# xmas_v2.net
KiCad netlist of a schematic drawn in EAGLE
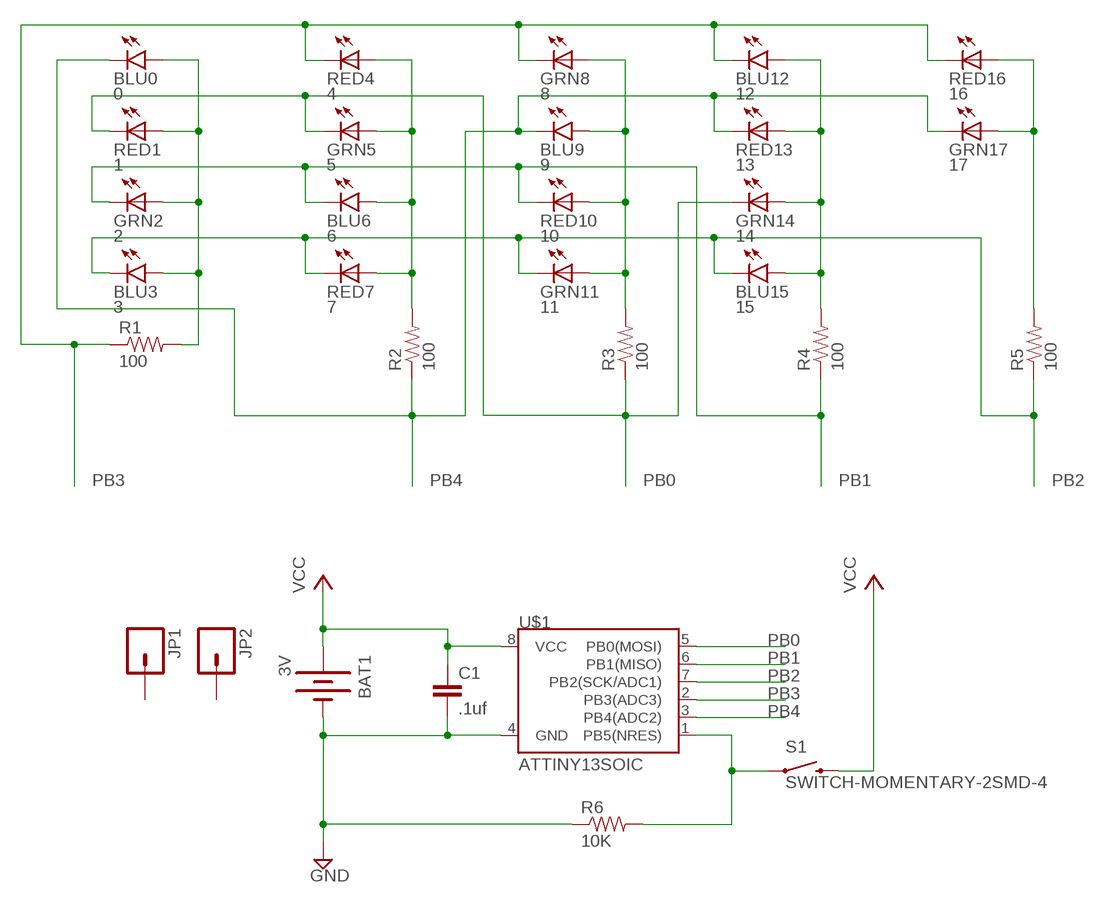
[diagram p0: schematic, sheet 1]

(export (version "E")
  (design (tool "Eeschema 10.0.6"))
  (components
    (comp (ref "BAT1")
      (value "3V")
      (footprint "eagle-import:BATTCOM_20MM_PTH")
      (libsource (lib "eagle-import") (part "BATTERY20PTH"))
    )
    (comp (ref "BLU0")
      (value "0")
      (footprint "eagle-import:LED5MM-KIT")
      (libsource (lib "eagle-import") (part "LED5MM-KIT"))
    )
    (comp (ref "BLU3")
      (value "3")
      (footprint "eagle-import:LED5MM-KIT")
      (libsource (lib "eagle-import") (part "LED5MM-KIT"))
    )
    (comp (ref "BLU6")
      (value "6")
      (footprint "eagle-import:LED5MM-KIT")
      (libsource (lib "eagle-import") (part "LED5MM-KIT"))
    )
    (comp (ref "BLU9")
      (value "9")
      (footprint "eagle-import:LED5MM-KIT")
      (libsource (lib "eagle-import") (part "LED5MM-KIT"))
    )
    (comp (ref "BLU12")
      (value "12")
      (footprint "eagle-import:LED5MM-KIT")
      (libsource (lib "eagle-import") (part "LED5MM-KIT"))
    )
    (comp (ref "BLU15")
      (value "15")
      (footprint "eagle-import:LED5MM-KIT")
      (libsource (lib "eagle-import") (part "LED5MM-KIT"))
    )
    (comp (ref "C1")
      (value ".1uf")
      (footprint "eagle-import:0805")
      (libsource (lib "eagle-import") (part "CAP0805"))
    )
    (comp (ref "GRN2")
      (value "2")
      (footprint "eagle-import:CHIPLED_0805")
      (libsource (lib "eagle-import") (part "LEDCHIPLED_0805"))
    )
    (comp (ref "GRN5")
      (value "5")
      (footprint "eagle-import:CHIPLED_0805")
      (libsource (lib "eagle-import") (part "LEDCHIPLED_0805"))
    )
    (comp (ref "GRN8")
      (value "8")
      (footprint "eagle-import:CHIPLED_0805")
      (libsource (lib "eagle-import") (part "LEDCHIPLED_0805"))
    )
    (comp (ref "GRN11")
      (value "11")
      (footprint "eagle-import:CHIPLED_0805")
      (libsource (lib "eagle-import") (part "LEDCHIPLED_0805"))
    )
    (comp (ref "GRN14")
      (value "14")
      (footprint "eagle-import:CHIPLED_0805")
      (libsource (lib "eagle-import") (part "LEDCHIPLED_0805"))
    )
    (comp (ref "GRN17")
      (value "17")
      (footprint "eagle-import:CHIPLED_0805")
      (libsource (lib "eagle-import") (part "LEDCHIPLED_0805"))
    )
    (comp (ref "JP1")
      (value "M01NOSILK-KIT")
      (footprint "eagle-import:1X01NS-KIT")
      (libsource (lib "eagle-import") (part "M01NOSILK-KIT"))
    )
    (comp (ref "JP2")
      (value "M01NOSILK-KIT")
      (footprint "eagle-import:1X01NS-KIT")
      (libsource (lib "eagle-import") (part "M01NOSILK-KIT"))
    )
    (comp (ref "R1")
      (value "100")
      (footprint "eagle-import:0805")
      (libsource (lib "eagle-import") (part "RESISTOR0805-RES"))
    )
    (comp (ref "R2")
      (value "100")
      (footprint "eagle-import:0805")
      (libsource (lib "eagle-import") (part "RESISTOR0805-RES"))
    )
    (comp (ref "R3")
      (value "100")
      (footprint "eagle-import:0805")
      (libsource (lib "eagle-import") (part "RESISTOR0805-RES"))
    )
    (comp (ref "R4")
      (value "100")
      (footprint "eagle-import:0805")
      (libsource (lib "eagle-import") (part "RESISTOR0805-RES"))
    )
    (comp (ref "R5")
      (value "100")
      (footprint "eagle-import:0805")
      (libsource (lib "eagle-import") (part "RESISTOR0805-RES"))
    )
    (comp (ref "R6")
      (value "10K")
      (footprint "eagle-import:0805")
      (libsource (lib "eagle-import") (part "RESISTOR0805-RES"))
    )
    (comp (ref "RED1")
      (value "1")
      (footprint "eagle-import:CHIPLED_0805")
      (libsource (lib "eagle-import") (part "LEDCHIPLED_0805"))
    )
    (comp (ref "RED4")
      (value "4")
      (footprint "eagle-import:CHIPLED_0805")
      (libsource (lib "eagle-import") (part "LEDCHIPLED_0805"))
    )
    (comp (ref "RED7")
      (value "7")
      (footprint "eagle-import:CHIPLED_0805")
      (libsource (lib "eagle-import") (part "LEDCHIPLED_0805"))
    )
    (comp (ref "RED10")
      (value "10")
      (footprint "eagle-import:CHIPLED_0805")
      (libsource (lib "eagle-import") (part "LEDCHIPLED_0805"))
    )
    (comp (ref "RED13")
      (value "13")
      (footprint "eagle-import:CHIPLED_0805")
      (libsource (lib "eagle-import") (part "LEDCHIPLED_0805"))
    )
    (comp (ref "RED16")
      (value "16")
      (footprint "eagle-import:CHIPLED_0805")
      (libsource (lib "eagle-import") (part "LEDCHIPLED_0805"))
    )
    (comp (ref "S1")
      (value "SWITCH-MOMENTARY-2SMD-4")
      (footprint "eagle-import:TACTILE_SWITCH_TALL")
      (libsource (lib "eagle-import") (part "SWITCH-MOMENTARY-2SMD-4"))
    )
    (comp (ref "U$1")
      (value "ATTINY13SOIC")
      (footprint "eagle-import:SO08")
      (libsource (lib "eagle-import") (part "ATTINY13SOIC"))
    )
  )
  (nets
    (net (code "1") (name "/PB0") (class "Default")
      (node (ref "GRN14") (pin "C") (pinfunction "C_C") (pintype "passive"))
      (node (ref "GRN5") (pin "C") (pinfunction "C_C") (pintype "passive"))
      (node (ref "R3") (pin "1") (pinfunction "1_1") (pintype "passive"))
      (node (ref "RED1") (pin "C") (pinfunction "C_C") (pintype "passive"))
      (node (ref "U$1") (pin "5") (pinfunction "PB0(MOSI)_5") (pintype "bidirectional"))
    )
    (net (code "2") (name "/PB1") (class "Default")
      (node (ref "BLU6") (pin "K") (pinfunction "C_K") (pintype "passive"))
      (node (ref "GRN2") (pin "C") (pinfunction "C_C") (pintype "passive"))
      (node (ref "R4") (pin "1") (pinfunction "1_1") (pintype "passive"))
      (node (ref "RED10") (pin "C") (pinfunction "C_C") (pintype "passive"))
      (node (ref "U$1") (pin "6") (pinfunction "PB1(MISO)_6") (pintype "bidirectional"))
    )
    (net (code "3") (name "/PB2") (class "Default")
      (node (ref "BLU15") (pin "K") (pinfunction "C_K") (pintype "passive"))
      (node (ref "BLU3") (pin "K") (pinfunction "C_K") (pintype "passive"))
      (node (ref "GRN11") (pin "C") (pinfunction "C_C") (pintype "passive"))
      (node (ref "R5") (pin "1") (pinfunction "1_1") (pintype "passive"))
      (node (ref "RED7") (pin "C") (pinfunction "C_C") (pintype "passive"))
      (node (ref "U$1") (pin "7") (pinfunction "PB2(SCK/ADC1)_7") (pintype "bidirectional"))
    )
    (net (code "4") (name "/PB3") (class "Default")
      (node (ref "BLU12") (pin "K") (pinfunction "C_K") (pintype "passive"))
      (node (ref "GRN8") (pin "C") (pinfunction "C_C") (pintype "passive"))
      (node (ref "R1") (pin "1") (pinfunction "1_1") (pintype "passive"))
      (node (ref "RED16") (pin "C") (pinfunction "C_C") (pintype "passive"))
      (node (ref "RED4") (pin "C") (pinfunction "C_C") (pintype "passive"))
      (node (ref "U$1") (pin "2") (pinfunction "PB3(ADC3)_2") (pintype "bidirectional"))
    )
    (net (code "5") (name "/PB4") (class "Default")
      (node (ref "BLU0") (pin "K") (pinfunction "C_K") (pintype "passive"))
      (node (ref "BLU9") (pin "K") (pinfunction "C_K") (pintype "passive"))
      (node (ref "GRN17") (pin "C") (pinfunction "C_C") (pintype "passive"))
      (node (ref "R2") (pin "1") (pinfunction "1_1") (pintype "passive"))
      (node (ref "RED13") (pin "C") (pinfunction "C_C") (pintype "passive"))
      (node (ref "U$1") (pin "3") (pinfunction "PB4(ADC2)_3") (pintype "bidirectional"))
    )
    (net (code "6") (name "GND") (class "Default")
      (node (ref "BAT1") (pin "2") (pinfunction "-_2") (pintype "power_in"))
      (node (ref "C1") (pin "2") (pinfunction "2_2") (pintype "passive"))
      (node (ref "R6") (pin "1") (pinfunction "1_1") (pintype "passive"))
      (node (ref "U$1") (pin "4") (pinfunction "GND_4") (pintype "bidirectional"))
    )
    (net (code "7") (name "Net-(BLU0-PadA)") (class "Default")
      (node (ref "BLU0") (pin "A") (pinfunction "A_A") (pintype "passive"))
      (node (ref "BLU3") (pin "A") (pinfunction "A_A") (pintype "passive"))
      (node (ref "GRN2") (pin "A") (pinfunction "A_A") (pintype "passive"))
      (node (ref "R1") (pin "2") (pinfunction "2_2") (pintype "passive"))
      (node (ref "RED1") (pin "A") (pinfunction "A_A") (pintype "passive"))
    )
    (net (code "8") (name "Net-(BLU6-PadA)") (class "Default")
      (node (ref "BLU6") (pin "A") (pinfunction "A_A") (pintype "passive"))
      (node (ref "GRN5") (pin "A") (pinfunction "A_A") (pintype "passive"))
      (node (ref "R2") (pin "2") (pinfunction "2_2") (pintype "passive"))
      (node (ref "RED4") (pin "A") (pinfunction "A_A") (pintype "passive"))
      (node (ref "RED7") (pin "A") (pinfunction "A_A") (pintype "passive"))
    )
    (net (code "9") (name "Net-(BLU9-PadA)") (class "Default")
      (node (ref "BLU9") (pin "A") (pinfunction "A_A") (pintype "passive"))
      (node (ref "GRN11") (pin "A") (pinfunction "A_A") (pintype "passive"))
      (node (ref "GRN8") (pin "A") (pinfunction "A_A") (pintype "passive"))
      (node (ref "R3") (pin "2") (pinfunction "2_2") (pintype "passive"))
      (node (ref "RED10") (pin "A") (pinfunction "A_A") (pintype "passive"))
    )
    (net (code "10") (name "Net-(BLU12-PadA)") (class "Default")
      (node (ref "BLU12") (pin "A") (pinfunction "A_A") (pintype "passive"))
      (node (ref "BLU15") (pin "A") (pinfunction "A_A") (pintype "passive"))
      (node (ref "GRN14") (pin "A") (pinfunction "A_A") (pintype "passive"))
      (node (ref "R4") (pin "2") (pinfunction "2_2") (pintype "passive"))
      (node (ref "RED13") (pin "A") (pinfunction "A_A") (pintype "passive"))
    )
    (net (code "11") (name "Net-(GRN17-PadA)") (class "Default")
      (node (ref "GRN17") (pin "A") (pinfunction "A_A") (pintype "passive"))
      (node (ref "R5") (pin "2") (pinfunction "2_2") (pintype "passive"))
      (node (ref "RED16") (pin "A") (pinfunction "A_A") (pintype "passive"))
    )
    (net (code "12") (name "Net-(S1-1)") (class "Default")
      (node (ref "R6") (pin "2") (pinfunction "2_2") (pintype "passive"))
      (node (ref "S1") (pin "A2") (pinfunction "1_A2") (pintype "passive"))
      (node (ref "U$1") (pin "1") (pinfunction "PB5(NRES)_1") (pintype "bidirectional"))
    )
    (net (code "13") (name "VCC") (class "Default")
      (node (ref "BAT1") (pin "1") (pinfunction "+_1") (pintype "power_in"))
      (node (ref "C1") (pin "1") (pinfunction "1_1") (pintype "passive"))
      (node (ref "S1") (pin "B2") (pinfunction "2_B2") (pintype "passive"))
      (node (ref "U$1") (pin "8") (pinfunction "VCC_8") (pintype "bidirectional"))
    )
    (net (code "14") (name "unconnected-(JP1-Pad1)") (class "Default")
      (node (ref "JP1") (pin "1") (pinfunction "1_1") (pintype "passive"))
    )
    (net (code "15") (name "unconnected-(JP2-Pad1)") (class "Default")
      (node (ref "JP2") (pin "1") (pinfunction "1_1") (pintype "passive"))
    )
  )
)
